# Audio_Amp_Rev_A.net
KiCad netlist of a schematic drawn in EAGLE
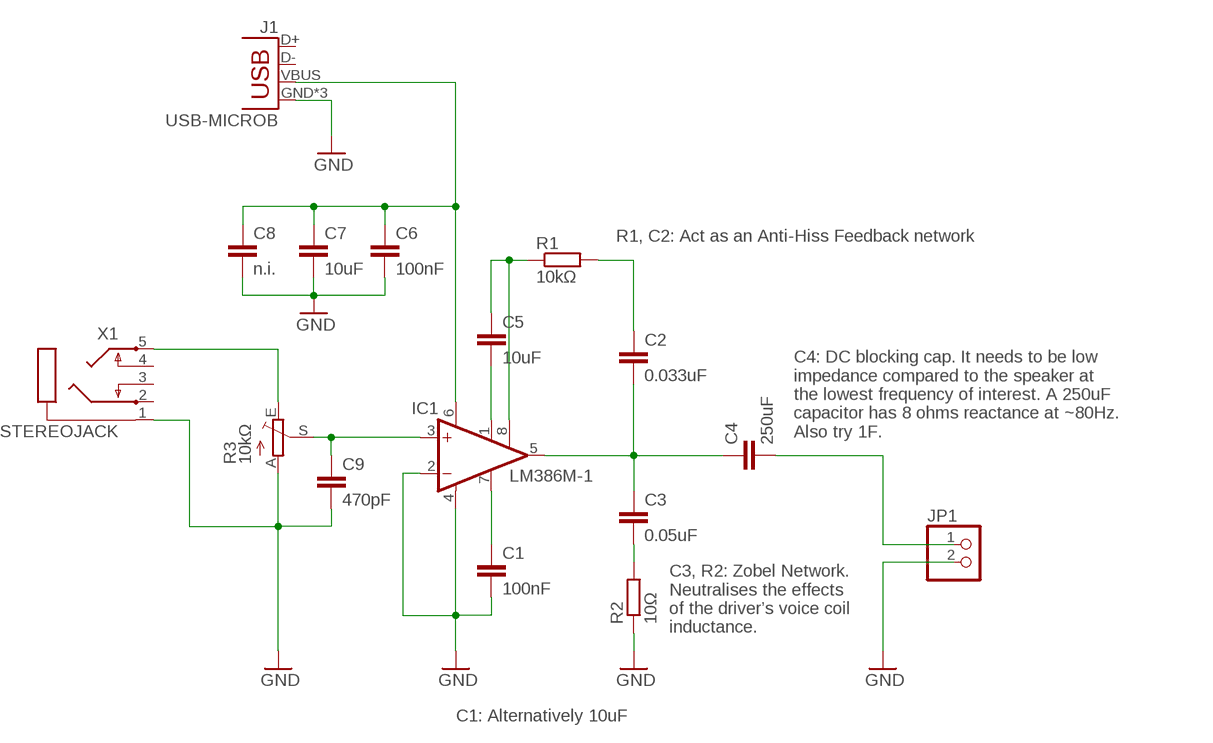
[diagram p0: schematic, sheet 1]

(export (version "E")
  (design (tool "Eeschema 10.0.6"))
  (components
    (comp (ref "C1")
      (value "100nF")
      (footprint "eagle-import:C0805")
      (libsource (lib "eagle-import") (part "C-EUC0805"))
    )
    (comp (ref "C2")
      (value "0.033uF")
      (footprint "eagle-import:C0805")
      (libsource (lib "eagle-import") (part "C-EUC0805"))
    )
    (comp (ref "C3")
      (value "0.05uF")
      (footprint "eagle-import:C0805")
      (libsource (lib "eagle-import") (part "C-EUC0805"))
    )
    (comp (ref "C4")
      (value "250uF")
      (footprint "eagle-import:C0805")
      (libsource (lib "eagle-import") (part "C-EUC0805"))
    )
    (comp (ref "C5")
      (value "10uF")
      (footprint "eagle-import:C0805")
      (libsource (lib "eagle-import") (part "C-EUC0805"))
    )
    (comp (ref "C6")
      (value "100nF")
      (footprint "eagle-import:C0805")
      (libsource (lib "eagle-import") (part "C-EUC0805"))
    )
    (comp (ref "C7")
      (value "10uF")
      (footprint "eagle-import:C0805")
      (libsource (lib "eagle-import") (part "C-EUC0805"))
    )
    (comp (ref "C8")
      (value "n.i.")
      (footprint "eagle-import:C0805")
      (libsource (lib "eagle-import") (part "C-EUC0805"))
    )
    (comp (ref "C9")
      (value "470pF")
      (footprint "eagle-import:C0805")
      (libsource (lib "eagle-import") (part "C-EUC0805"))
    )
    (comp (ref "IC1")
      (value "LM386M-1")
      (footprint "eagle-import:SO08")
      (libsource (lib "eagle-import") (part "LM386?-M1"))
    )
    (comp (ref "J1")
      (value "USB-MICROB")
      (footprint "eagle-import:USB-MICROB")
      (libsource (lib "eagle-import") (part "USB-MICROB"))
    )
    (comp (ref "JP1")
      (value "PINHD-1X2")
      (footprint "eagle-import:1X02")
      (libsource (lib "eagle-import") (part "PINHD-1X2"))
    )
    (comp (ref "R1")
      (value "10kΩ")
      (footprint "eagle-import:R0805")
      (libsource (lib "eagle-import") (part "R-EU_R0805"))
    )
    (comp (ref "R2")
      (value "10Ω")
      (footprint "eagle-import:R0805")
      (libsource (lib "eagle-import") (part "R-EU_R0805"))
    )
    (comp (ref "R3")
      (value "10kΩ")
      (footprint "eagle-import:CIP20C-6MM")
      (libsource (lib "eagle-import") (part "TRIM_EU-CIP20C-6MM"))
    )
    (comp (ref "X1")
      (value "STEREOJACK")
      (footprint "eagle-import:STX3100")
      (libsource (lib "eagle-import") (part "STEREOJACK"))
    )
  )
  (nets
    (net (code "1") (name "GND") (class "Default")
      (node (ref "C1") (pin "2") (pinfunction "2_2") (pintype "passive"))
      (node (ref "C6") (pin "2") (pinfunction "2_2") (pintype "passive"))
      (node (ref "C7") (pin "2") (pinfunction "2_2") (pintype "passive"))
      (node (ref "C8") (pin "2") (pinfunction "2_2") (pintype "passive"))
      (node (ref "C9") (pin "2") (pinfunction "2_2") (pintype "passive"))
      (node (ref "IC1") (pin "2") (pinfunction "-IN_2") (pintype "input"))
      (node (ref "IC1") (pin "4") (pinfunction "GND_4") (pintype "power_in"))
      (node (ref "J1") (pin "GND") (pinfunction "GND_GND") (pintype "bidirectional"))
      (node (ref "J1") (pin "MT1") (pinfunction "GND_MT1") (pintype "bidirectional"))
      (node (ref "J1") (pin "MT2") (pinfunction "GND_MT2") (pintype "bidirectional"))
      (node (ref "JP1") (pin "2") (pinfunction "2_2") (pintype "passive"))
      (node (ref "R2") (pin "1") (pinfunction "1_1") (pintype "passive"))
      (node (ref "R3") (pin "A") (pinfunction "A_A") (pintype "passive"))
      (node (ref "X1") (pin "1") (pinfunction "1_1") (pintype "passive"))
    )
    (net (code "2") (name "Net-(C2-Pad1)") (class "Default")
      (node (ref "C2") (pin "1") (pinfunction "1_1") (pintype "passive"))
      (node (ref "R1") (pin "2") (pinfunction "2_2") (pintype "passive"))
    )
    (net (code "3") (name "Net-(C3-Pad2)") (class "Default")
      (node (ref "C3") (pin "2") (pinfunction "2_2") (pintype "passive"))
      (node (ref "R2") (pin "2") (pinfunction "2_2") (pintype "passive"))
    )
    (net (code "4") (name "Net-(C4-Pad2)") (class "Default")
      (node (ref "C4") (pin "2") (pinfunction "2_2") (pintype "passive"))
      (node (ref "JP1") (pin "1") (pinfunction "1_1") (pintype "passive"))
    )
    (net (code "5") (name "Net-(C5-Pad1)") (class "Default")
      (node (ref "C5") (pin "1") (pinfunction "1_1") (pintype "passive"))
      (node (ref "IC1") (pin "8") (pinfunction "GAIN_8") (pintype "passive"))
      (node (ref "R1") (pin "1") (pinfunction "1_1") (pintype "passive"))
    )
    (net (code "6") (name "Net-(C5-Pad2)") (class "Default")
      (node (ref "C5") (pin "2") (pinfunction "2_2") (pintype "passive"))
      (node (ref "IC1") (pin "1") (pinfunction "GAIN_1") (pintype "passive"))
    )
    (net (code "7") (name "Net-(IC1-+IN)") (class "Default")
      (node (ref "C9") (pin "1") (pinfunction "1_1") (pintype "passive"))
      (node (ref "IC1") (pin "3") (pinfunction "+IN_3") (pintype "input"))
      (node (ref "R3") (pin "S") (pinfunction "S_S") (pintype "passive"))
    )
    (net (code "8") (name "Net-(IC1-BYPASS)") (class "Default")
      (node (ref "C1") (pin "1") (pinfunction "1_1") (pintype "passive"))
      (node (ref "IC1") (pin "7") (pinfunction "BYPASS_7") (pintype "passive"))
    )
    (net (code "9") (name "Net-(IC1-OUT)") (class "Default")
      (node (ref "C2") (pin "2") (pinfunction "2_2") (pintype "passive"))
      (node (ref "C3") (pin "1") (pinfunction "1_1") (pintype "passive"))
      (node (ref "C4") (pin "1") (pinfunction "1_1") (pintype "passive"))
      (node (ref "IC1") (pin "5") (pinfunction "OUT_5") (pintype "output"))
    )
    (net (code "10") (name "Net-(IC1-VS)") (class "Default")
      (node (ref "C6") (pin "1") (pinfunction "1_1") (pintype "passive"))
      (node (ref "C7") (pin "1") (pinfunction "1_1") (pintype "passive"))
      (node (ref "C8") (pin "1") (pinfunction "1_1") (pintype "passive"))
      (node (ref "IC1") (pin "6") (pinfunction "VS_6") (pintype "power_in"))
      (node (ref "J1") (pin "VBUS") (pinfunction "VBUS_VBUS") (pintype "bidirectional"))
    )
    (net (code "11") (name "Net-(R3-PadE)") (class "Default")
      (node (ref "R3") (pin "E") (pinfunction "E_E") (pintype "passive"))
      (node (ref "X1") (pin "5") (pinfunction "5_5") (pintype "passive"))
    )
    (net (code "12") (name "unconnected-(J1-PadD+)") (class "Default")
      (node (ref "J1") (pin "D+") (pinfunction "D+_D+") (pintype "bidirectional"))
    )
    (net (code "13") (name "unconnected-(J1-PadD-)") (class "Default")
      (node (ref "J1") (pin "D-") (pinfunction "D-_D-") (pintype "bidirectional"))
    )
    (net (code "14") (name "unconnected-(X1-Pad2)") (class "Default")
      (node (ref "X1") (pin "2") (pinfunction "2_2") (pintype "passive"))
    )
    (net (code "15") (name "unconnected-(X1-Pad3)") (class "Default")
      (node (ref "X1") (pin "3") (pinfunction "3_3") (pintype "passive"))
    )
    (net (code "16") (name "unconnected-(X1-Pad4)") (class "Default")
      (node (ref "X1") (pin "4") (pinfunction "4_4") (pintype "passive"))
    )
  )
)
